# NB2_PBCON.net
KiCad netlist of a schematic drawn in Altium Designer
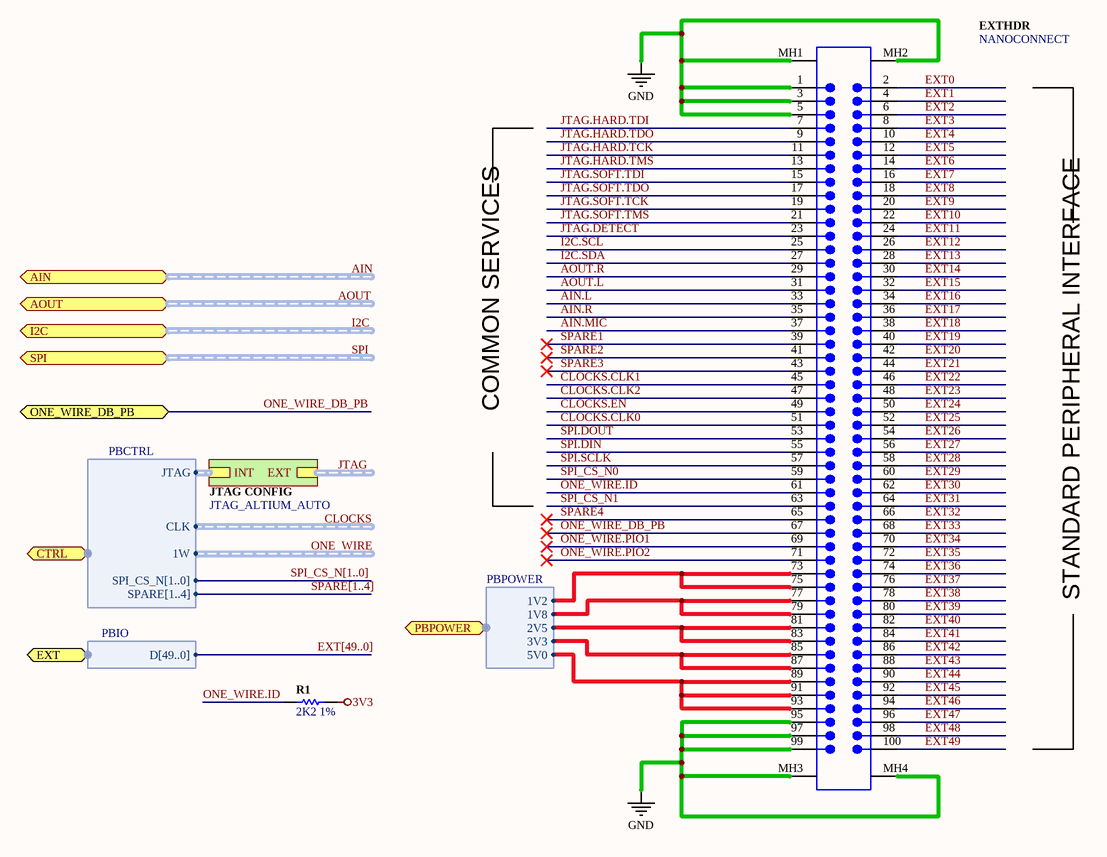
[diagram p0: NB2_PBCON.schdoc]

(export (version "E")
  (design (tool "Eeschema 10.0.6"))
  (components
    (comp (ref "EXTHDR")
      (value "NANOCONNECT")
      (footprint "53751")
      (description "Connector, Molex Docking Station 100 Pin Female 53751")
      (libsource (lib "altium-import") (part "root_0_CON-DOCKSTAT-100-F-STR_"))
    )
    (comp (ref "R1")
      (value "2K2 1%")
      (footprint "RESC1005-STAR")
      (description "Resistor, 2K2 1% 0402 (1005)")
      (fields (field (name "TOLERANCE") "1 %"))
      (libsource (lib "AltiumDesignLibrary") (part "RES"))
    )
  )
  (nets
    (net (code "12") (name "/AIN.L") (class "Default")
      (node (ref "EXTHDR") (pin "33") (pinfunction "33_33") (pintype "passive"))
    )
    (net (code "13") (name "/AIN.MIC") (class "Default")
      (node (ref "EXTHDR") (pin "37") (pinfunction "37_37") (pintype "passive"))
    )
    (net (code "14") (name "/AIN.R") (class "Default")
      (node (ref "EXTHDR") (pin "35") (pinfunction "35_35") (pintype "passive"))
    )
    (net (code "15") (name "/AOUT.L") (class "Default")
      (node (ref "EXTHDR") (pin "31") (pinfunction "31_31") (pintype "passive"))
    )
    (net (code "16") (name "/AOUT.R") (class "Default")
      (node (ref "EXTHDR") (pin "29") (pinfunction "29_29") (pintype "passive"))
    )
    (net (code "17") (name "/CLOCKS.CLK0") (class "Default")
      (node (ref "EXTHDR") (pin "51") (pinfunction "51_51") (pintype "passive"))
    )
    (net (code "18") (name "/CLOCKS.CLK1") (class "Default")
      (node (ref "EXTHDR") (pin "45") (pinfunction "45_45") (pintype "passive"))
    )
    (net (code "19") (name "/CLOCKS.CLK2") (class "Default")
      (node (ref "EXTHDR") (pin "47") (pinfunction "47_47") (pintype "passive"))
    )
    (net (code "20") (name "/CLOCKS.EN") (class "Default")
      (node (ref "EXTHDR") (pin "49") (pinfunction "49_49") (pintype "passive"))
    )
    (net (code "22") (name "/EXT0") (class "Default")
      (node (ref "EXTHDR") (pin "2") (pinfunction "2_2") (pintype "passive"))
    )
    (net (code "23") (name "/EXT1") (class "Default")
      (node (ref "EXTHDR") (pin "4") (pinfunction "4_4") (pintype "passive"))
    )
    (net (code "24") (name "/EXT2") (class "Default")
      (node (ref "EXTHDR") (pin "6") (pinfunction "6_6") (pintype "passive"))
    )
    (net (code "25") (name "/EXT3") (class "Default")
      (node (ref "EXTHDR") (pin "8") (pinfunction "8_8") (pintype "passive"))
    )
    (net (code "26") (name "/EXT4") (class "Default")
      (node (ref "EXTHDR") (pin "10") (pinfunction "10_10") (pintype "passive"))
    )
    (net (code "27") (name "/EXT5") (class "Default")
      (node (ref "EXTHDR") (pin "12") (pinfunction "12_12") (pintype "passive"))
    )
    (net (code "28") (name "/EXT6") (class "Default")
      (node (ref "EXTHDR") (pin "14") (pinfunction "14_14") (pintype "passive"))
    )
    (net (code "29") (name "/EXT7") (class "Default")
      (node (ref "EXTHDR") (pin "16") (pinfunction "16_16") (pintype "passive"))
    )
    (net (code "30") (name "/EXT8") (class "Default")
      (node (ref "EXTHDR") (pin "18") (pinfunction "18_18") (pintype "passive"))
    )
    (net (code "31") (name "/EXT9") (class "Default")
      (node (ref "EXTHDR") (pin "20") (pinfunction "20_20") (pintype "passive"))
    )
    (net (code "32") (name "/EXT10") (class "Default")
      (node (ref "EXTHDR") (pin "22") (pinfunction "22_22") (pintype "passive"))
    )
    (net (code "33") (name "/EXT11") (class "Default")
      (node (ref "EXTHDR") (pin "24") (pinfunction "24_24") (pintype "passive"))
    )
    (net (code "34") (name "/EXT12") (class "Default")
      (node (ref "EXTHDR") (pin "26") (pinfunction "26_26") (pintype "passive"))
    )
    (net (code "35") (name "/EXT13") (class "Default")
      (node (ref "EXTHDR") (pin "28") (pinfunction "28_28") (pintype "passive"))
    )
    (net (code "36") (name "/EXT14") (class "Default")
      (node (ref "EXTHDR") (pin "30") (pinfunction "30_30") (pintype "passive"))
    )
    (net (code "37") (name "/EXT15") (class "Default")
      (node (ref "EXTHDR") (pin "32") (pinfunction "32_32") (pintype "passive"))
    )
    (net (code "38") (name "/EXT16") (class "Default")
      (node (ref "EXTHDR") (pin "34") (pinfunction "34_34") (pintype "passive"))
    )
    (net (code "39") (name "/EXT17") (class "Default")
      (node (ref "EXTHDR") (pin "36") (pinfunction "36_36") (pintype "passive"))
    )
    (net (code "40") (name "/EXT18") (class "Default")
      (node (ref "EXTHDR") (pin "38") (pinfunction "38_38") (pintype "passive"))
    )
    (net (code "41") (name "/EXT19") (class "Default")
      (node (ref "EXTHDR") (pin "40") (pinfunction "40_40") (pintype "passive"))
    )
    (net (code "42") (name "/EXT20") (class "Default")
      (node (ref "EXTHDR") (pin "42") (pinfunction "42_42") (pintype "passive"))
    )
    (net (code "43") (name "/EXT21") (class "Default")
      (node (ref "EXTHDR") (pin "44") (pinfunction "44_44") (pintype "passive"))
    )
    (net (code "44") (name "/EXT22") (class "Default")
      (node (ref "EXTHDR") (pin "46") (pinfunction "46_46") (pintype "passive"))
    )
    (net (code "45") (name "/EXT23") (class "Default")
      (node (ref "EXTHDR") (pin "48") (pinfunction "48_48") (pintype "passive"))
    )
    (net (code "46") (name "/EXT24") (class "Default")
      (node (ref "EXTHDR") (pin "50") (pinfunction "50_50") (pintype "passive"))
    )
    (net (code "47") (name "/EXT25") (class "Default")
      (node (ref "EXTHDR") (pin "52") (pinfunction "52_52") (pintype "passive"))
    )
    (net (code "48") (name "/EXT26") (class "Default")
      (node (ref "EXTHDR") (pin "54") (pinfunction "54_54") (pintype "passive"))
    )
    (net (code "49") (name "/EXT27") (class "Default")
      (node (ref "EXTHDR") (pin "56") (pinfunction "56_56") (pintype "passive"))
    )
    (net (code "50") (name "/EXT28") (class "Default")
      (node (ref "EXTHDR") (pin "58") (pinfunction "58_58") (pintype "passive"))
    )
    (net (code "51") (name "/EXT29") (class "Default")
      (node (ref "EXTHDR") (pin "60") (pinfunction "60_60") (pintype "passive"))
    )
    (net (code "52") (name "/EXT30") (class "Default")
      (node (ref "EXTHDR") (pin "62") (pinfunction "62_62") (pintype "passive"))
    )
    (net (code "53") (name "/EXT31") (class "Default")
      (node (ref "EXTHDR") (pin "64") (pinfunction "64_64") (pintype "passive"))
    )
    (net (code "54") (name "/EXT32") (class "Default")
      (node (ref "EXTHDR") (pin "66") (pinfunction "66_66") (pintype "passive"))
    )
    (net (code "55") (name "/EXT33") (class "Default")
      (node (ref "EXTHDR") (pin "68") (pinfunction "68_68") (pintype "passive"))
    )
    (net (code "56") (name "/EXT34") (class "Default")
      (node (ref "EXTHDR") (pin "70") (pinfunction "70_70") (pintype "passive"))
    )
    (net (code "57") (name "/EXT35") (class "Default")
      (node (ref "EXTHDR") (pin "72") (pinfunction "72_72") (pintype "passive"))
    )
    (net (code "58") (name "/EXT36") (class "Default")
      (node (ref "EXTHDR") (pin "74") (pinfunction "74_74") (pintype "passive"))
    )
    (net (code "59") (name "/EXT37") (class "Default")
      (node (ref "EXTHDR") (pin "76") (pinfunction "76_76") (pintype "passive"))
    )
    (net (code "60") (name "/EXT38") (class "Default")
      (node (ref "EXTHDR") (pin "78") (pinfunction "78_78") (pintype "passive"))
    )
    (net (code "61") (name "/EXT39") (class "Default")
      (node (ref "EXTHDR") (pin "80") (pinfunction "80_80") (pintype "passive"))
    )
    (net (code "62") (name "/EXT40") (class "Default")
      (node (ref "EXTHDR") (pin "82") (pinfunction "82_82") (pintype "passive"))
    )
    (net (code "63") (name "/EXT41") (class "Default")
      (node (ref "EXTHDR") (pin "84") (pinfunction "84_84") (pintype "passive"))
    )
    (net (code "64") (name "/EXT42") (class "Default")
      (node (ref "EXTHDR") (pin "86") (pinfunction "86_86") (pintype "passive"))
    )
    (net (code "65") (name "/EXT43") (class "Default")
      (node (ref "EXTHDR") (pin "88") (pinfunction "88_88") (pintype "passive"))
    )
    (net (code "66") (name "/EXT44") (class "Default")
      (node (ref "EXTHDR") (pin "90") (pinfunction "90_90") (pintype "passive"))
    )
    (net (code "67") (name "/EXT45") (class "Default")
      (node (ref "EXTHDR") (pin "92") (pinfunction "92_92") (pintype "passive"))
    )
    (net (code "68") (name "/EXT46") (class "Default")
      (node (ref "EXTHDR") (pin "94") (pinfunction "94_94") (pintype "passive"))
    )
    (net (code "69") (name "/EXT47") (class "Default")
      (node (ref "EXTHDR") (pin "96") (pinfunction "96_96") (pintype "passive"))
    )
    (net (code "70") (name "/EXT48") (class "Default")
      (node (ref "EXTHDR") (pin "98") (pinfunction "98_98") (pintype "passive"))
    )
    (net (code "71") (name "/EXT49") (class "Default")
      (node (ref "EXTHDR") (pin "100") (pinfunction "100_100") (pintype "passive"))
    )
    (net (code "73") (name "/I2C.SCL") (class "Default")
      (node (ref "EXTHDR") (pin "25") (pinfunction "25_25") (pintype "passive"))
    )
    (net (code "74") (name "/I2C.SDA") (class "Default")
      (node (ref "EXTHDR") (pin "27") (pinfunction "27_27") (pintype "passive"))
    )
    (net (code "75") (name "/JTAG.DETECT") (class "Default")
      (node (ref "EXTHDR") (pin "23") (pinfunction "23_23") (pintype "passive"))
    )
    (net (code "76") (name "/JTAG.HARD.TCK") (class "Default")
      (node (ref "EXTHDR") (pin "11") (pinfunction "11_11") (pintype "passive"))
    )
    (net (code "77") (name "/JTAG.HARD.TDI") (class "Default")
      (node (ref "EXTHDR") (pin "7") (pinfunction "7_7") (pintype "passive"))
    )
    (net (code "78") (name "/JTAG.HARD.TDO") (class "Default")
      (node (ref "EXTHDR") (pin "9") (pinfunction "9_9") (pintype "passive"))
    )
    (net (code "79") (name "/JTAG.HARD.TMS") (class "Default")
      (node (ref "EXTHDR") (pin "13") (pinfunction "13_13") (pintype "passive"))
    )
    (net (code "80") (name "/JTAG.SOFT.TCK") (class "Default")
      (node (ref "EXTHDR") (pin "19") (pinfunction "19_19") (pintype "passive"))
    )
    (net (code "81") (name "/JTAG.SOFT.TDI") (class "Default")
      (node (ref "EXTHDR") (pin "15") (pinfunction "15_15") (pintype "passive"))
    )
    (net (code "82") (name "/JTAG.SOFT.TDO") (class "Default")
      (node (ref "EXTHDR") (pin "17") (pinfunction "17_17") (pintype "passive"))
    )
    (net (code "83") (name "/JTAG.SOFT.TMS") (class "Default")
      (node (ref "EXTHDR") (pin "21") (pinfunction "21_21") (pintype "passive"))
    )
    (net (code "84") (name "/ONE_WIRE.ID") (class "Default")
      (node (ref "EXTHDR") (pin "61") (pinfunction "61_61") (pintype "passive"))
      (node (ref "R1") (pin "1") (pinfunction "1_1") (pintype "passive"))
    )
    (net (code "85") (name "/ONE_WIRE.PIO1") (class "Default")
      (node (ref "EXTHDR") (pin "69") (pinfunction "69_69") (pintype "passive+no_connect"))
    )
    (net (code "86") (name "/ONE_WIRE.PIO2") (class "Default")
      (node (ref "EXTHDR") (pin "71") (pinfunction "71_71") (pintype "passive+no_connect"))
    )
    (net (code "87") (name "/ONE_WIRE_DB_PB") (class "Default")
      (node (ref "EXTHDR") (pin "67") (pinfunction "67_67") (pintype "passive+no_connect"))
    )
    (net (code "88") (name "/SPARE1") (class "Default")
      (node (ref "EXTHDR") (pin "39") (pinfunction "39_39") (pintype "passive+no_connect"))
    )
    (net (code "89") (name "/SPARE2") (class "Default")
      (node (ref "EXTHDR") (pin "41") (pinfunction "41_41") (pintype "passive+no_connect"))
    )
    (net (code "90") (name "/SPARE3") (class "Default")
      (node (ref "EXTHDR") (pin "43") (pinfunction "43_43") (pintype "passive+no_connect"))
    )
    (net (code "91") (name "/SPARE4") (class "Default")
      (node (ref "EXTHDR") (pin "65") (pinfunction "65_65") (pintype "passive+no_connect"))
    )
    (net (code "93") (name "/SPI.DIN") (class "Default")
      (node (ref "EXTHDR") (pin "55") (pinfunction "55_55") (pintype "passive"))
    )
    (net (code "94") (name "/SPI.DOUT") (class "Default")
      (node (ref "EXTHDR") (pin "53") (pinfunction "53_53") (pintype "passive"))
    )
    (net (code "95") (name "/SPI.SCLK") (class "Default")
      (node (ref "EXTHDR") (pin "57") (pinfunction "57_57") (pintype "passive"))
    )
    (net (code "96") (name "/SPI_CS_N0") (class "Default")
      (node (ref "EXTHDR") (pin "59") (pinfunction "59_59") (pintype "passive"))
    )
    (net (code "97") (name "/SPI_CS_N1") (class "Default")
      (node (ref "EXTHDR") (pin "63") (pinfunction "63_63") (pintype "passive"))
    )
    (net (code "109") (name "3V3") (class "Default")
      (node (ref "R1") (pin "2") (pinfunction "2_2") (pintype "passive"))
    )
    (net (code "110") (name "GND") (class "Default")
      (node (ref "EXTHDR") (pin "1") (pinfunction "1_1") (pintype "passive"))
      (node (ref "EXTHDR") (pin "3") (pinfunction "3_3") (pintype "passive"))
      (node (ref "EXTHDR") (pin "5") (pinfunction "5_5") (pintype "passive"))
      (node (ref "EXTHDR") (pin "95") (pinfunction "95_95") (pintype "passive"))
      (node (ref "EXTHDR") (pin "97") (pinfunction "97_97") (pintype "passive"))
      (node (ref "EXTHDR") (pin "99") (pinfunction "99_99") (pintype "passive"))
      (node (ref "EXTHDR") (pin "MH1") (pinfunction "MH1_MH1") (pintype "passive"))
      (node (ref "EXTHDR") (pin "MH2") (pinfunction "MH2_MH2") (pintype "passive"))
      (node (ref "EXTHDR") (pin "MH3") (pinfunction "MH3_MH3") (pintype "passive"))
      (node (ref "EXTHDR") (pin "MH4") (pinfunction "MH4_MH4") (pintype "passive"))
    )
    (net (code "111") (name "Net-(EXTHDR-Pad73)") (class "Default")
      (node (ref "EXTHDR") (pin "73") (pinfunction "73_73") (pintype "passive"))
      (node (ref "EXTHDR") (pin "75") (pinfunction "75_75") (pintype "passive"))
    )
    (net (code "112") (name "Net-(EXTHDR-Pad77)") (class "Default")
      (node (ref "EXTHDR") (pin "77") (pinfunction "77_77") (pintype "passive"))
      (node (ref "EXTHDR") (pin "79") (pinfunction "79_79") (pintype "passive"))
    )
    (net (code "113") (name "Net-(EXTHDR-Pad81)") (class "Default")
      (node (ref "EXTHDR") (pin "81") (pinfunction "81_81") (pintype "passive"))
      (node (ref "EXTHDR") (pin "83") (pinfunction "83_83") (pintype "passive"))
    )
    (net (code "114") (name "Net-(EXTHDR-Pad85)") (class "Default")
      (node (ref "EXTHDR") (pin "85") (pinfunction "85_85") (pintype "passive"))
      (node (ref "EXTHDR") (pin "87") (pinfunction "87_87") (pintype "passive"))
    )
    (net (code "115") (name "Net-(EXTHDR-Pad89)") (class "Default")
      (node (ref "EXTHDR") (pin "89") (pinfunction "89_89") (pintype "passive"))
      (node (ref "EXTHDR") (pin "91") (pinfunction "91_91") (pintype "passive"))
      (node (ref "EXTHDR") (pin "93") (pinfunction "93_93") (pintype "passive"))
    )
  )
)
